# Humidifier_Schematic.net
KiCad netlist of a schematic drawn in Altium Designer
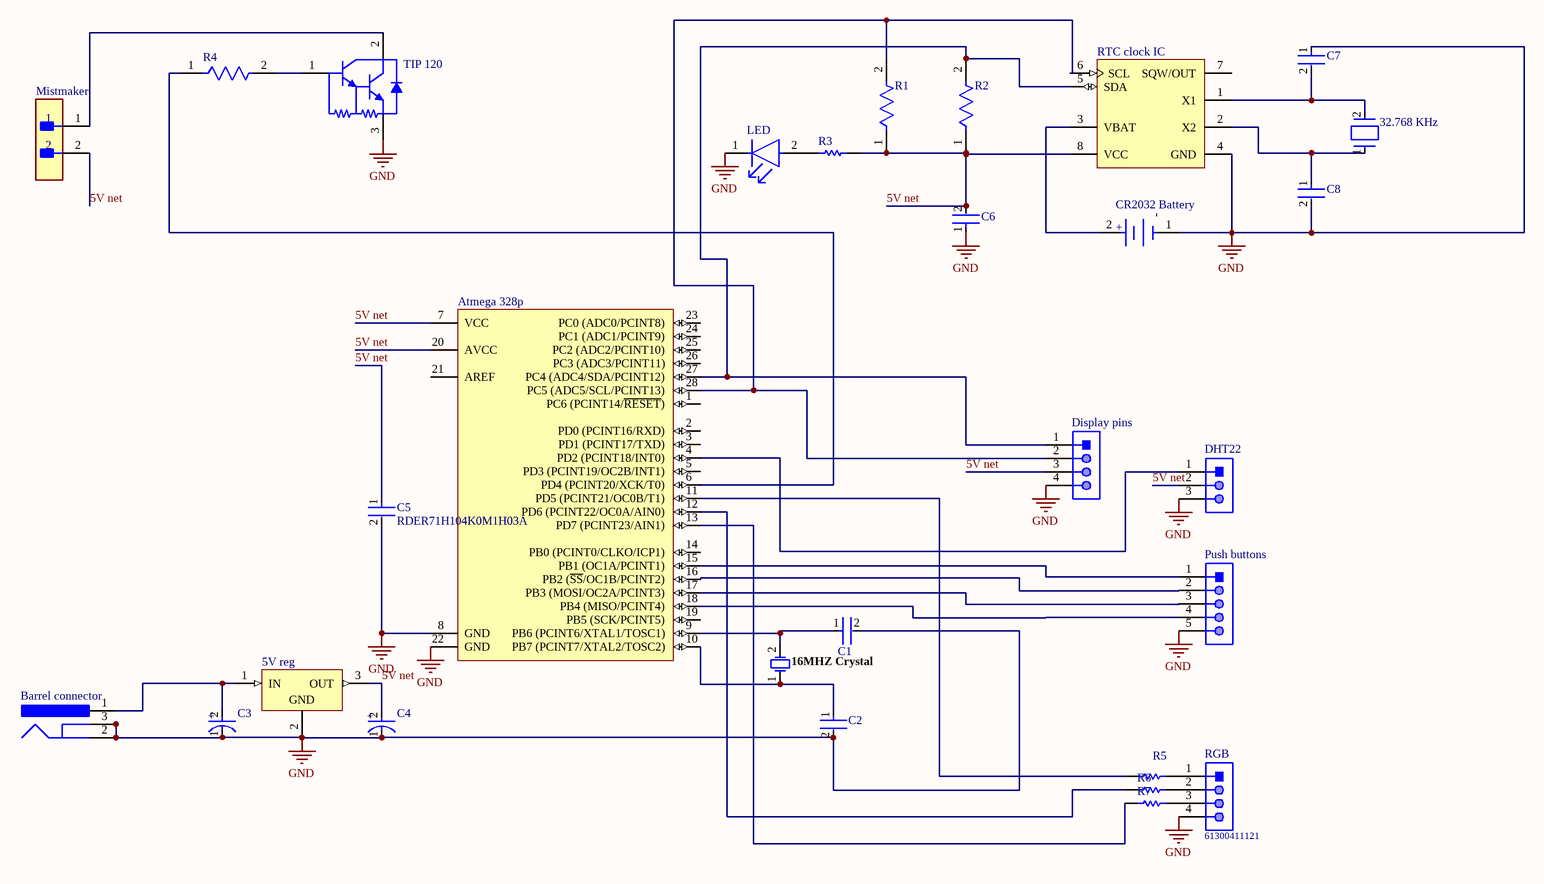
[diagram p0: Humidifier_Schematic.SchDoc]

(export (version "E")
  (design (tool "Eeschema 10.0.6"))
  (components
    (comp (ref "5V reg")
      (value "LM7805CT")
      (footprint "FAIR-TO-220-3")
      (description "Positive Voltage Regulator, 5 V, 1 A, -40 to 125 degC, 3-Pin TO-220, RoHS, Tube")
      (fields (field (name "MANUFACTURER") "FairchildSemiconductor"))
      (libsource (lib "Altium Content Vault") (part "FAIR-LM7805CT-TO220-3"))
    )
    (comp (ref "16MHZ Crystal")
      (value "FOXSLF/160-20")
      (footprint "FOX-FOXSLF160-20")
      (description "Resistance Weld Thru-Hole Crystal, 16 MHz, -20 to 70 degC, 2-Pin THD, RoHS, Bulk")
      (fields (field (name "TOLERANCE") "1%"))
      (libsource (lib "Altium Content Vault") (part "XTAL-1-2-2"))
    )
    (comp (ref "32.768 KHz")
      (value "AB26TRB-32.768KHZ-T")
      (footprint "FP-AB26TRB-MFG")
      (description "CRYSTAL 32.7680KHZ 12.5PF TH")
      (fields (field (name "TOLERANCE") "20ppm"))
      (libsource (lib "Altium Content Vault") (part "c23a69dc6c9e2f18f2079038eb95dd1"))
    )
    (comp (ref "Atmega 328p")
      (value "ATmega328-PU")
      (footprint "28P3")
      (libsource (lib "Altium Content Vault") (part "MC-8B-ATM48-IL28"))
    )
    (comp (ref "Barrel connector")
      (value "PJ-002A")
      (footprint "CUI-PJ-002A_V")
      (fields (field (name "MANUFACTURER") "CUIInc."))
      (libsource (lib "Altium Content Vault") (part "JACK-2CD3-RN_B"))
    )
    (comp (ref "C1")
      (value "RCE5C1H220J0K1H03B")
      (footprint "FP-RCE0K1-MFG")
      (description "Cap Ceramic 22pF 50V C0G ±5% Radial 5mm +125°C Automotive Bulk")
      (fields (field (name "TOLERANCE") "5%"))
      (libsource (lib "Altium Content Vault") (part "b4654b650e69147ec39a6b967a45e02"))
    )
    (comp (ref "C2")
      (value "RCE5C1H220J0K1H03B")
      (footprint "FP-RCE0K1-MFG")
      (description "Cap Ceramic 22pF 50V C0G ±5% Radial 5mm +125°C Automotive Bulk")
      (fields (field (name "TOLERANCE") "5%"))
      (libsource (lib "Altium Content Vault") (part "b4654b650e69147ec39a6b967a45e02"))
    )
    (comp (ref "C3")
      (value "EEUFR1A472L")
      (footprint "FP-RAD-TH-D_12_5_0_5-L_30-MFG")
      (description "Aluminum Electrolytic Capacitors (Radial Lead Type) 4700uF ±20% 10V")
      (fields (field (name "TOLERANCE") "20%") (field (name "VOLTAGE") "10V"))
      (libsource (lib "Altium Content Vault") (part "203bc49f2ac43e59fd269a8c329ed05"))
    )
    (comp (ref "C4")
      (value "EEUFR1A472L")
      (footprint "FP-RAD-TH-D_12_5_0_5-L_30-MFG")
      (description "Aluminum Electrolytic Capacitors (Radial Lead Type) 4700uF ±20% 10V")
      (fields (field (name "TOLERANCE") "20%") (field (name "VOLTAGE") "10V"))
      (libsource (lib "Altium Content Vault") (part "203bc49f2ac43e59fd269a8c329ed05"))
    )
    (comp (ref "C5")
      (value "RDER71H104K0M1H03A")
      (footprint "FP-RDE0M1-MFG")
      (description "Ceramic Capacitor 100nF ±10% 50V X7R Radial")
      (fields (field (name "TOLERANCE") "10%"))
      (libsource (lib "Altium Content Vault") (part "b4654b650e69147ec39a6b967a45e02"))
    )
    (comp (ref "C6")
      (value "RCER71H104K0K1H03B")
      (footprint "FP-RCE0K1-MFG")
      (description "Cap Ceramic 100nF 50V X7R ±10% Radial 5mm +125°C Automotive Bulk")
      (fields (field (name "VOLTAGE") "50V") (field (name "TOLERANCE") "10%"))
      (libsource (lib "Altium Content Vault") (part "b4654b650e69147ec39a6b967a45e02"))
    )
    (comp (ref "C7")
      (value "RCE5C1H120J0DBH03A")
      (footprint "FP-RCE0DB-MFG")
      (description "Cap Ceramic 12pF 50V C0G ±5% Radial 2.5mm +125°C Ammo Pack")
      (fields (field (name "TOLERANCE") "5%"))
      (libsource (lib "Altium Content Vault") (part "b4654b650e69147ec39a6b967a45e02"))
    )
    (comp (ref "C8")
      (value "RCE5C1H120J0DBH03A")
      (footprint "FP-RCE0DB-MFG")
      (description "Cap Ceramic 12pF 50V C0G ±5% Radial 2.5mm +125°C Ammo Pack")
      (fields (field (name "TOLERANCE") "5%"))
      (libsource (lib "Altium Content Vault") (part "b4654b650e69147ec39a6b967a45e02"))
    )
    (comp (ref "CR2032 Battery")
      (value "BU2032SM-HD-G")
      (footprint "FP-BU2032SM-HD-G-MFG")
      (description "BATTERY HOLDER COIN 20MM SMD")
      (libsource (lib "Altium Content Vault") (part "60d3b5b901a8747834971d0eb8cf3fd"))
    )
    (comp (ref "DHT22")
      (value "61300311121")
      (footprint "61300311121")
      (description "THT Vertical Pin Header WR-PHD, Pitch 2.54 mm, Single Row, 3 pins")
      (fields (field (name "MANUFACTURER") "Wurth Elektronik") (field (name "PUBLISHER") "WurthElektronik"))
      (libsource (lib "Altium Content Vault") (part "WE-CN-1P-M-R3"))
    )
    (comp (ref "Display pins")
      (value "61300411121")
      (footprint "61300411121")
      (description "THT Vertical Pin Header WR-PHD, Pitch 2.54 mm, Single Row, 4 pins")
      (fields (field (name "MANUFACTURER") "Wurth Elektronik") (field (name "PUBLISHER") "WurthElektronik"))
      (libsource (lib "Altium Content Vault") (part "WE-CN-1P-M-R4"))
    )
    (comp (ref "LED")
      (value "HLMP-1503")
      (footprint "FP-HLMP-1503-MFG")
      (description "LED GREEN DIFFUSED T-1 T/H")
      (fields
        (field (name "MANUFACTURER") "Broadcom")
        (field (name "OCTOPART") "https://octopart.com/hlmp-1503-broadcom-71130371")
      )
      (libsource (lib "Altium Content Vault") (part "8706943c75ba83719d021d2fdc84c58"))
    )
    (comp (ref "Mistmaker")
      (value "M20-9990246")
      (footprint "FP-M20-9990246-MFG")
      (description "CONN HEADER VERT 2POS 2.54MM")
      (fields
        (field (name "OCTOPART") "https://octopart.com/m20-9990246-harwin-2590635")
        (field (name "MANUFACTURER") "Harwin")
      )
      (libsource (lib "Altium Content Vault") (part "3bc925449376181038e59eaffc5286c"))
    )
    (comp (ref "Push buttons")
      (value "61300511121")
      (footprint "61300511121")
      (description "THT Vertical Pin Header WR-PHD, Pitch 2.54 mm, Single Row, 5 pins")
      (fields (field (name "MANUFACTURER") "Wurth Elektronik") (field (name "PUBLISHER") "WurthElektronik"))
      (libsource (lib "Altium Content Vault") (part "WE-CN-1P-M-R5"))
    )
    (comp (ref "R1")
      (value "CF18JT2K20")
      (footprint "FP-CF18-MFG")
      (description "RES 2.2K OHM 1/8W 5% CF AXIAL")
      (fields
        (field (name "OCTOPART") "https://octopart.com/cf18jt2k20-stackpole+electronics-19205714")
        (field (name "TOLERANCE") "5%")
      )
      (libsource (lib "Altium Content Vault") (part "1029c3af85768c4190bb7ad29bc67b5"))
    )
    (comp (ref "R2")
      (value "CF18JT2K20")
      (footprint "FP-CF18-MFG")
      (description "RES 2.2K OHM 1/8W 5% CF AXIAL")
      (fields
        (field (name "OCTOPART") "https://octopart.com/cf18jt2k20-stackpole+electronics-19205714")
        (field (name "TOLERANCE") "5%")
      )
      (libsource (lib "Altium Content Vault") (part "1029c3af85768c4190bb7ad29bc67b5"))
    )
    (comp (ref "R3")
      (value "MFR-25FBF52-1K")
      (footprint "RESA60-630X240")
      (description "Axial Resistor, 1 KOhm, +/- 1%, 250 mW, -55 to 155 degC, 2-Pin THD, RoHS, Bulk")
      (fields (field (name "TOLERANCE") "1%"))
      (libsource (lib "Altium Content Vault") (part "RES-2"))
    )
    (comp (ref "R4")
      (value "CF18JT2K20")
      (footprint "FP-CF18-MFG")
      (description "RES 2.2K OHM 1/8W 5% CF AXIAL")
      (fields
        (field (name "OCTOPART") "https://octopart.com/cf18jt2k20-stackpole+electronics-19205714")
        (field (name "TOLERANCE") "5%")
      )
      (libsource (lib "Altium Content Vault") (part "1029c3af85768c4190bb7ad29bc67b5"))
    )
    (comp (ref "R5")
      (value "MFR-25FBF52-1K")
      (footprint "RESA60-630X240")
      (description "Axial Resistor, 1 KOhm, +/- 1%, 250 mW, -55 to 155 degC, 2-Pin THD, RoHS, Bulk")
      (fields (field (name "TOLERANCE") "1%"))
      (libsource (lib "Altium Content Vault") (part "RES-2"))
    )
    (comp (ref "R6")
      (value "MFR-25FBF52-1K")
      (footprint "RESA60-630X240")
      (description "Axial Resistor, 1 KOhm, +/- 1%, 250 mW, -55 to 155 degC, 2-Pin THD, RoHS, Bulk")
      (fields (field (name "TOLERANCE") "1%"))
      (libsource (lib "Altium Content Vault") (part "RES-2"))
    )
    (comp (ref "R7")
      (value "MFR-25FBF52-1K")
      (footprint "RESA60-630X240")
      (description "Axial Resistor, 1 KOhm, +/- 1%, 250 mW, -55 to 155 degC, 2-Pin THD, RoHS, Bulk")
      (fields (field (name "TOLERANCE") "1%"))
      (libsource (lib "Altium Content Vault") (part "RES-2"))
    )
    (comp (ref "RGB")
      (value "61300411121")
      (footprint "61300411121")
      (description "THT Vertical Pin Header WR-PHD, Pitch 2.54 mm, Single Row, 4 pins")
      (fields (field (name "MANUFACTURER") "Wurth Elektronik") (field (name "PUBLISHER") "WurthElektronik"))
      (libsource (lib "Altium Content Vault") (part "WE-CN-1P-M-R4"))
    )
    (comp (ref "RTC clock IC")
      (value "DS1307+")
      (footprint "P8+2")
      (description "64 x 8, Serial, I2C Real-Time Clock, 5.0V, 8-Pin PDIP, 0 to 70 degC, Pb-Free")
      (libsource (lib "Altium Content Vault") (part "PR_RTC_DS1307-IL8"))
    )
    (comp (ref "TIP 120")
      (value "TIP120G")
      (footprint "ONSC-TO-220-3-221A-09")
      (description "Plastic Medium-Power, Complementary Silicon Transistor, 3-Pin TO-220, Pb-Free, Tube")
      (fields (field (name "MANUFACTURER") "On Semiconductor"))
      (libsource (lib "Altium Content Vault") (part "ONSC-DT-NPN-B1C2E3-3_A"))
    )
  )
  (nets
    (net (code "1") (name "/5V net") (class "Default")
      (node (ref "5V reg") (pin "3") (pinfunction "OUT_3") (pintype "output"))
      (node (ref "Atmega 328p") (pin "20") (pinfunction "AVCC_20") (pintype "power_in"))
      (node (ref "Atmega 328p") (pin "7") (pinfunction "VCC_7") (pintype "power_in"))
      (node (ref "C4") (pin "2") (pinfunction "A_2") (pintype "passive"))
      (node (ref "C5") (pin "1") (pinfunction "1_1") (pintype "passive"))
      (node (ref "C6") (pin "2") (pinfunction "2_2") (pintype "passive"))
      (node (ref "DHT22") (pin "2") (pinfunction "2_2") (pintype "passive"))
      (node (ref "Display pins") (pin "3") (pinfunction "3_3") (pintype "passive"))
      (node (ref "Mistmaker") (pin "2") (pinfunction "2_2") (pintype "passive"))
      (node (ref "R1") (pin "1") (pinfunction "1_1") (pintype "passive"))
      (node (ref "R2") (pin "1") (pinfunction "1_1") (pintype "passive"))
      (node (ref "R3") (pin "2") (pinfunction "2_2") (pintype "passive"))
      (node (ref "RTC clock IC") (pin "8") (pinfunction "VCC_8") (pintype "power_in"))
    )
    (net (code "2") (name "GND") (class "Default")
      (node (ref "5V reg") (pin "2") (pinfunction "GND_2") (pintype "power_in"))
      (node (ref "Atmega 328p") (pin "22") (pinfunction "GND_22") (pintype "power_in"))
      (node (ref "Atmega 328p") (pin "8") (pinfunction "GND_8") (pintype "power_in"))
      (node (ref "Barrel connector") (pin "2") (pinfunction "2_2") (pintype "passive"))
      (node (ref "Barrel connector") (pin "3") (pinfunction "3_3") (pintype "passive"))
      (node (ref "C1") (pin "2") (pinfunction "2_2") (pintype "passive"))
      (node (ref "C2") (pin "2") (pinfunction "2_2") (pintype "passive"))
      (node (ref "C3") (pin "1") (pinfunction "C_1") (pintype "passive"))
      (node (ref "C4") (pin "1") (pinfunction "C_1") (pintype "passive"))
      (node (ref "C5") (pin "2") (pinfunction "2_2") (pintype "passive"))
      (node (ref "C6") (pin "1") (pinfunction "1_1") (pintype "passive"))
      (node (ref "C7") (pin "1") (pinfunction "1_1") (pintype "passive"))
      (node (ref "C8") (pin "2") (pinfunction "2_2") (pintype "passive"))
      (node (ref "CR2032 Battery") (pin "1") (pinfunction "C_1") (pintype "passive"))
      (node (ref "DHT22") (pin "3") (pinfunction "3_3") (pintype "passive"))
      (node (ref "Display pins") (pin "4") (pinfunction "4_4") (pintype "passive"))
      (node (ref "LED") (pin "1") (pinfunction "C_1") (pintype "passive"))
      (node (ref "Push buttons") (pin "5") (pinfunction "5_5") (pintype "passive"))
      (node (ref "RGB") (pin "4") (pinfunction "4_4") (pintype "passive"))
      (node (ref "RTC clock IC") (pin "4") (pinfunction "GND_4") (pintype "power_in"))
      (node (ref "TIP 120") (pin "3") (pinfunction "E_3") (pintype "passive"))
    )
    (net (code "3") (name "Net-(5V reg-IN)") (class "Default")
      (node (ref "5V reg") (pin "1") (pinfunction "IN_1") (pintype "input"))
      (node (ref "Barrel connector") (pin "1") (pinfunction "1_1") (pintype "passive"))
      (node (ref "C3") (pin "2") (pinfunction "A_2") (pintype "passive"))
    )
    (net (code "4") (name "Net-(Atmega 328p-PB1_(OC1A{slash}PCINT1))") (class "Default")
      (node (ref "Atmega 328p") (pin "15") (pinfunction "PB1_(OC1A/PCINT1)_15") (pintype "bidirectional"))
      (node (ref "Push buttons") (pin "1") (pinfunction "1_1") (pintype "passive"))
    )
    (net (code "5") (name "Net-(Atmega 328p-PB2_(~{SS}{slash}OC1B{slash}PCINT2))") (class "Default")
      (node (ref "Atmega 328p") (pin "16") (pinfunction "PB2_(~{SS}/OC1B/PCINT2)_16") (pintype "bidirectional"))
      (node (ref "Push buttons") (pin "2") (pinfunction "2_2") (pintype "passive"))
    )
    (net (code "6") (name "Net-(Atmega 328p-PB3_(MOSI{slash}OC2A{slash}PCINT3))") (class "Default")
      (node (ref "Atmega 328p") (pin "17") (pinfunction "PB3_(MOSI/OC2A/PCINT3)_17") (pintype "bidirectional"))
      (node (ref "Push buttons") (pin "3") (pinfunction "3_3") (pintype "passive"))
    )
    (net (code "7") (name "Net-(Atmega 328p-PB4_(MISO{slash}PCINT4))") (class "Default")
      (node (ref "Atmega 328p") (pin "18") (pinfunction "PB4_(MISO/PCINT4)_18") (pintype "bidirectional"))
      (node (ref "Push buttons") (pin "4") (pinfunction "4_4") (pintype "passive"))
    )
    (net (code "8") (name "Net-(Atmega 328p-PB6_(PCINT6{slash}XTAL1{slash}TOSC1))") (class "Default")
      (node (ref "16MHZ Crystal") (pin "2") (pinfunction "2_2") (pintype "passive"))
      (node (ref "Atmega 328p") (pin "9") (pinfunction "PB6_(PCINT6/XTAL1/TOSC1)_9") (pintype "bidirectional"))
      (node (ref "C1") (pin "1") (pinfunction "1_1") (pintype "passive"))
    )
    (net (code "9") (name "Net-(Atmega 328p-PB7_(PCINT7{slash}XTAL2{slash}TOSC2))") (class "Default")
      (node (ref "16MHZ Crystal") (pin "1") (pinfunction "1_1") (pintype "passive"))
      (node (ref "Atmega 328p") (pin "10") (pinfunction "PB7_(PCINT7/XTAL2/TOSC2)_10") (pintype "bidirectional"))
      (node (ref "C2") (pin "1") (pinfunction "1_1") (pintype "passive"))
    )
    (net (code "10") (name "Net-(Atmega 328p-PC4_(ADC4{slash}SDA{slash}PCINT12))") (class "Default")
      (node (ref "Atmega 328p") (pin "27") (pinfunction "PC4_(ADC4/SDA/PCINT12)_27") (pintype "bidirectional"))
      (node (ref "Display pins") (pin "1") (pinfunction "1_1") (pintype "passive"))
      (node (ref "R2") (pin "2") (pinfunction "2_2") (pintype "passive"))
      (node (ref "RTC clock IC") (pin "5") (pinfunction "SDA_5") (pintype "bidirectional"))
    )
    (net (code "11") (name "Net-(Atmega 328p-PC5_(ADC5{slash}SCL{slash}PCINT13))") (class "Default")
      (node (ref "Atmega 328p") (pin "28") (pinfunction "PC5_(ADC5/SCL/PCINT13)_28") (pintype "bidirectional"))
      (node (ref "Display pins") (pin "2") (pinfunction "2_2") (pintype "passive"))
      (node (ref "R1") (pin "2") (pinfunction "2_2") (pintype "passive"))
      (node (ref "RTC clock IC") (pin "6") (pinfunction "SCL_6") (pintype "input"))
    )
    (net (code "12") (name "Net-(Atmega 328p-PD2_(PCINT18{slash}INT0))") (class "Default")
      (node (ref "Atmega 328p") (pin "4") (pinfunction "PD2_(PCINT18/INT0)_4") (pintype "bidirectional"))
      (node (ref "DHT22") (pin "1") (pinfunction "1_1") (pintype "passive"))
    )
    (net (code "13") (name "Net-(Atmega 328p-PD4_(PCINT20{slash}XCK{slash}T0))") (class "Default")
      (node (ref "Atmega 328p") (pin "6") (pinfunction "PD4_(PCINT20/XCK/T0)_6") (pintype "bidirectional"))
      (node (ref "R4") (pin "1") (pinfunction "1_1") (pintype "passive"))
    )
    (net (code "14") (name "Net-(Atmega 328p-PD5_(PCINT21{slash}OC0B{slash}T1))") (class "Default")
      (node (ref "Atmega 328p") (pin "11") (pinfunction "PD5_(PCINT21/OC0B/T1)_11") (pintype "bidirectional"))
      (node (ref "R5") (pin "1") (pinfunction "1_1") (pintype "passive"))
    )
    (net (code "15") (name "Net-(Atmega 328p-PD6_(PCINT22{slash}OC0A{slash}AIN0))") (class "Default")
      (node (ref "Atmega 328p") (pin "12") (pinfunction "PD6_(PCINT22/OC0A/AIN0)_12") (pintype "bidirectional"))
      (node (ref "R6") (pin "1") (pinfunction "1_1") (pintype "passive"))
    )
    (net (code "16") (name "Net-(Atmega 328p-PD7_(PCINT23{slash}AIN1))") (class "Default")
      (node (ref "Atmega 328p") (pin "13") (pinfunction "PD7_(PCINT23/AIN1)_13") (pintype "bidirectional"))
      (node (ref "R7") (pin "1") (pinfunction "1_1") (pintype "passive"))
    )
    (net (code "17") (name "Net-(CR2032 Battery-A)") (class "Default")
      (node (ref "CR2032 Battery") (pin "2") (pinfunction "A_2") (pintype "passive"))
      (node (ref "RTC clock IC") (pin "3") (pinfunction "VBAT_3") (pintype "power_in"))
    )
    (net (code "18") (name "Net-(LED-A)") (class "Default")
      (node (ref "LED") (pin "2") (pinfunction "A_2") (pintype "passive"))
      (node (ref "R3") (pin "1") (pinfunction "1_1") (pintype "passive"))
    )
    (net (code "19") (name "Net-(R5-Pad2)") (class "Default")
      (node (ref "R5") (pin "2") (pinfunction "2_2") (pintype "passive"))
      (node (ref "RGB") (pin "1") (pinfunction "1_1") (pintype "passive"))
    )
    (net (code "20") (name "Net-(R6-Pad2)") (class "Default")
      (node (ref "R6") (pin "2") (pinfunction "2_2") (pintype "passive"))
      (node (ref "RGB") (pin "2") (pinfunction "2_2") (pintype "passive"))
    )
    (net (code "21") (name "Net-(R7-Pad2)") (class "Default")
      (node (ref "R7") (pin "2") (pinfunction "2_2") (pintype "passive"))
      (node (ref "RGB") (pin "3") (pinfunction "3_3") (pintype "passive"))
    )
    (net (code "22") (name "Net-(RTC clock IC-X1)") (class "Default")
      (node (ref "32.768 KHz") (pin "2") (pinfunction "2_2") (pintype "passive"))
      (node (ref "C7") (pin "2") (pinfunction "2_2") (pintype "passive"))
      (node (ref "RTC clock IC") (pin "1") (pinfunction "X1_1") (pintype "passive"))
    )
    (net (code "23") (name "Net-(RTC clock IC-X2)") (class "Default")
      (node (ref "32.768 KHz") (pin "1") (pinfunction "1_1") (pintype "passive"))
      (node (ref "C8") (pin "1") (pinfunction "1_1") (pintype "passive"))
      (node (ref "RTC clock IC") (pin "2") (pinfunction "X2_2") (pintype "passive"))
    )
    (net (code "24") (name "Net-(TIP 120-B)") (class "Default")
      (node (ref "R4") (pin "2") (pinfunction "2_2") (pintype "passive"))
      (node (ref "TIP 120") (pin "1") (pinfunction "B_1") (pintype "passive"))
    )
    (net (code "25") (name "Net-(TIP 120-C)") (class "Default")
      (node (ref "Mistmaker") (pin "1") (pinfunction "1_1") (pintype "passive"))
      (node (ref "TIP 120") (pin "2") (pinfunction "C_2") (pintype "passive"))
    )
    (net (code "26") (name "unconnected-(Atmega 328p-AREF-Pad21)") (class "Default")
      (node (ref "Atmega 328p") (pin "21") (pinfunction "AREF_21") (pintype "power_in"))
    )
    (net (code "27") (name "unconnected-(Atmega 328p-PB0_(PCINT0{slash}CLKO{slash}ICP1)-Pad14)") (class "Default")
      (node (ref "Atmega 328p") (pin "14") (pinfunction "PB0_(PCINT0/CLKO/ICP1)_14") (pintype "bidirectional"))
    )
    (net (code "28") (name "unconnected-(Atmega 328p-PB5_(SCK{slash}PCINT5)-Pad19)") (class "Default")
      (node (ref "Atmega 328p") (pin "19") (pinfunction "PB5_(SCK/PCINT5)_19") (pintype "bidirectional"))
    )
    (net (code "29") (name "unconnected-(Atmega 328p-PC0_(ADC0{slash}PCINT8)-Pad23)") (class "Default")
      (node (ref "Atmega 328p") (pin "23") (pinfunction "PC0_(ADC0/PCINT8)_23") (pintype "bidirectional"))
    )
    (net (code "30") (name "unconnected-(Atmega 328p-PC1_(ADC1{slash}PCINT9)-Pad24)") (class "Default")
      (node (ref "Atmega 328p") (pin "24") (pinfunction "PC1_(ADC1/PCINT9)_24") (pintype "bidirectional"))
    )
    (net (code "31") (name "unconnected-(Atmega 328p-PC2_(ADC2{slash}PCINT10)-Pad25)") (class "Default")
      (node (ref "Atmega 328p") (pin "25") (pinfunction "PC2_(ADC2/PCINT10)_25") (pintype "bidirectional"))
    )
    (net (code "32") (name "unconnected-(Atmega 328p-PC3_(ADC3{slash}PCINT11)-Pad26)") (class "Default")
      (node (ref "Atmega 328p") (pin "26") (pinfunction "PC3_(ADC3/PCINT11)_26") (pintype "bidirectional"))
    )
    (net (code "33") (name "unconnected-(Atmega 328p-PC6_(PCINT14{slash}~{RESET})-Pad1)") (class "Default")
      (node (ref "Atmega 328p") (pin "1") (pinfunction "PC6_(PCINT14/~{RESET})_1") (pintype "bidirectional"))
    )
    (net (code "34") (name "unconnected-(Atmega 328p-PD0_(PCINT16{slash}RXD)-Pad2)") (class "Default")
      (node (ref "Atmega 328p") (pin "2") (pinfunction "PD0_(PCINT16/RXD)_2") (pintype "bidirectional"))
    )
    (net (code "35") (name "unconnected-(Atmega 328p-PD1_(PCINT17{slash}TXD)-Pad3)") (class "Default")
      (node (ref "Atmega 328p") (pin "3") (pinfunction "PD1_(PCINT17/TXD)_3") (pintype "bidirectional"))
    )
    (net (code "36") (name "unconnected-(Atmega 328p-PD3_(PCINT19{slash}OC2B{slash}INT1)-Pad5)") (class "Default")
      (node (ref "Atmega 328p") (pin "5") (pinfunction "PD3_(PCINT19/OC2B/INT1)_5") (pintype "bidirectional"))
    )
    (net (code "37") (name "unconnected-(RTC clock IC-SQW{slash}OUT-Pad7)") (class "Default")
      (node (ref "RTC clock IC") (pin "7") (pinfunction "SQW/OUT_7") (pintype "open_collector"))
    )
  )
)
